# 2rfm69.net
KiCad netlist of a schematic drawn in EAGLE
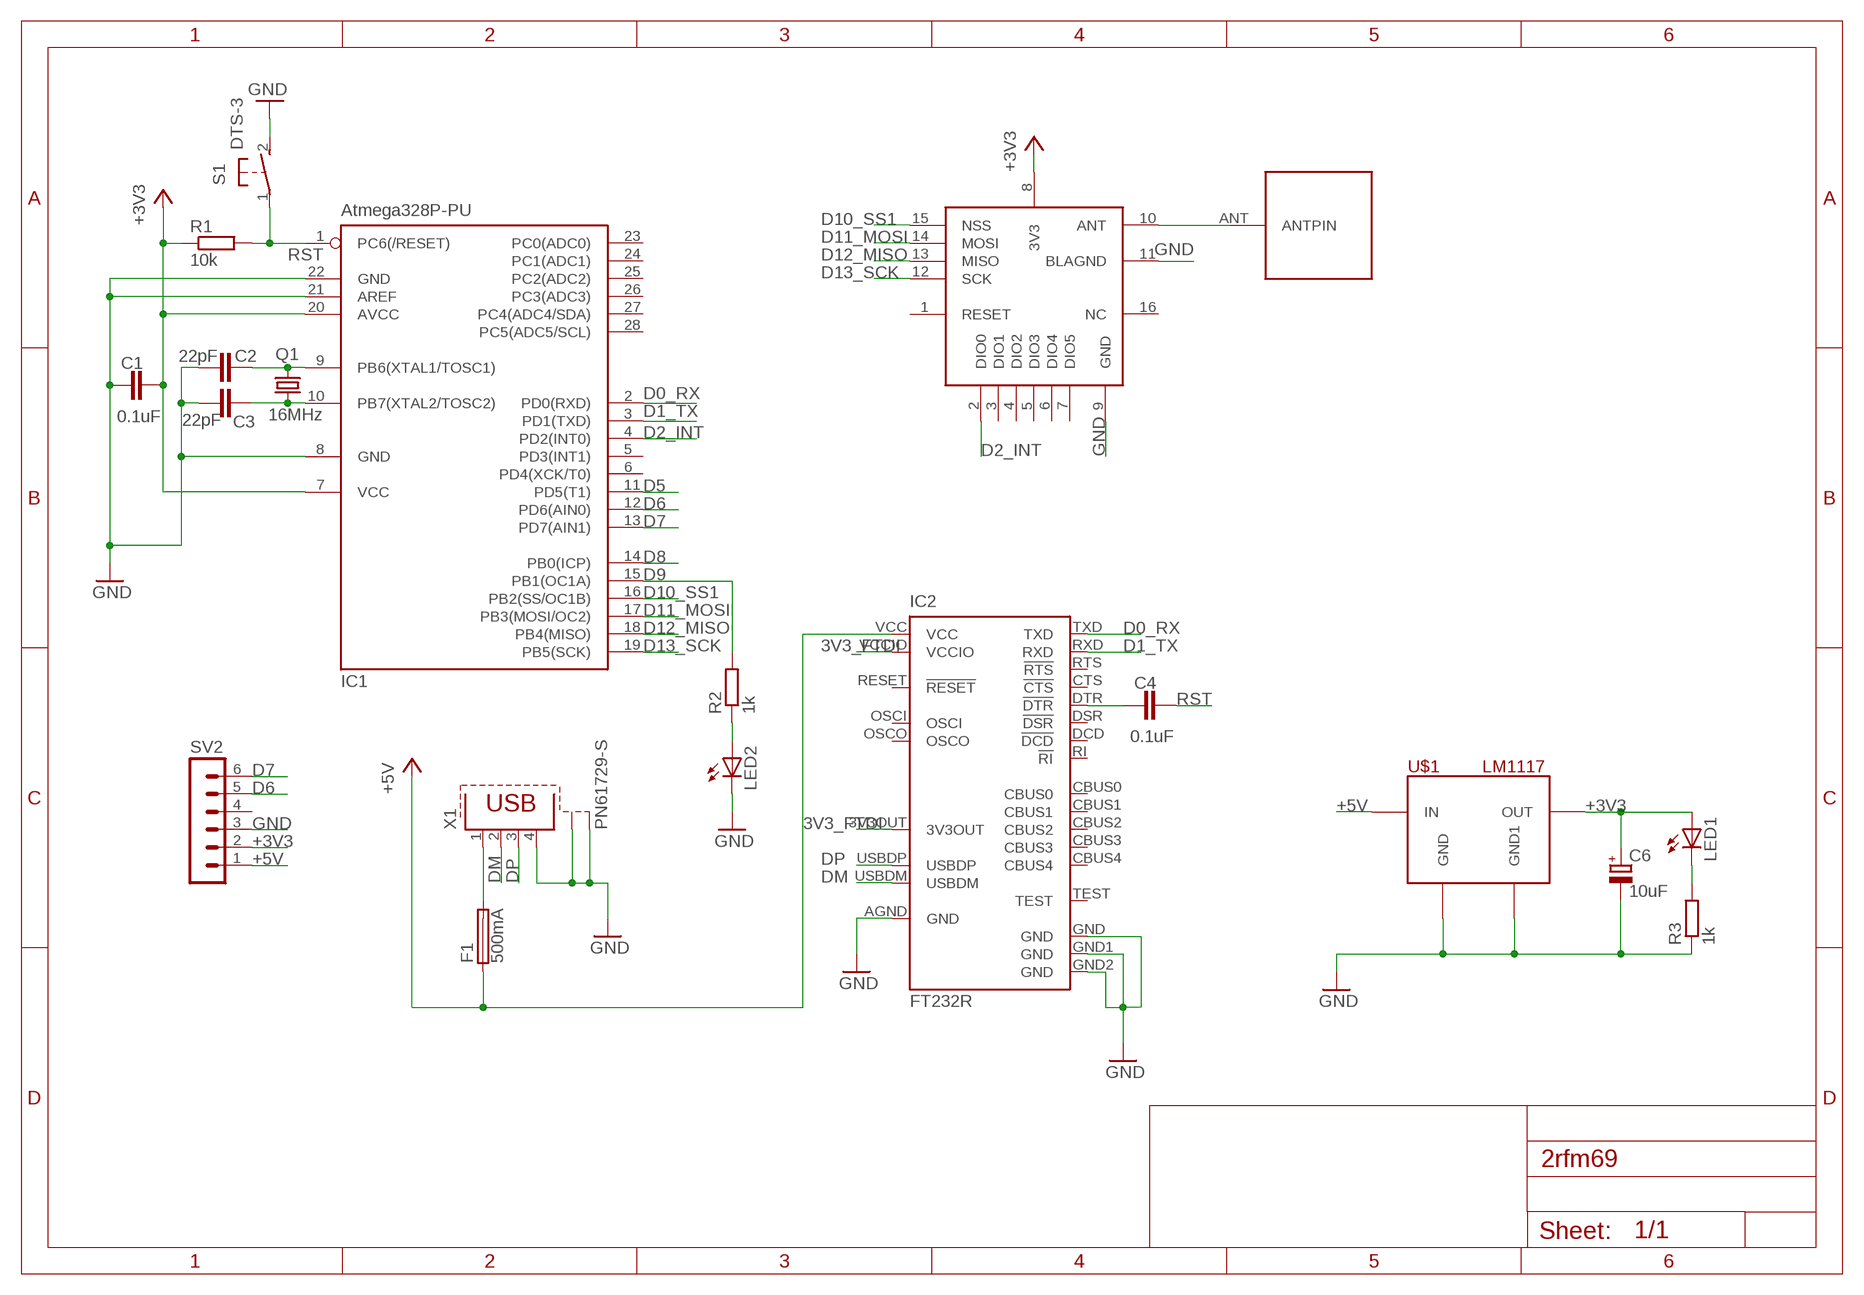
[diagram p0: schematic, sheet 1]

(export (version "E")
  (design (tool "Eeschema 10.0.6"))
  (components
    (comp (ref "C1")
      (value "0.1uF")
      (footprint "eagle-import:C050-025X075")
      (libsource (lib "eagle-import") (part "C-EU050-025X075"))
    )
    (comp (ref "C2")
      (value "22pF")
      (footprint "eagle-import:C050-025X075")
      (libsource (lib "eagle-import") (part "C-EU050-025X075"))
    )
    (comp (ref "C3")
      (value "22pF")
      (footprint "eagle-import:C050-025X075")
      (libsource (lib "eagle-import") (part "C-EU050-025X075"))
    )
    (comp (ref "C4")
      (value "0.1uF")
      (footprint "eagle-import:C050-025X075")
      (libsource (lib "eagle-import") (part "C-EU050-025X075"))
    )
    (comp (ref "C6")
      (value "10uF")
      (footprint "eagle-import:E2,5-6E")
      (libsource (lib "eagle-import") (part "CPOL-EUE2,5-6E"))
    )
    (comp (ref "F1")
      (value "500mA")
      (footprint "eagle-import:TE5")
      (libsource (lib "eagle-import") (part "TE5"))
    )
    (comp (ref "IC1")
      (value "Atmega328P-PU")
      (footprint "eagle-import:DIL28-3")
      (libsource (lib "eagle-import") (part "MEGA8-P"))
    )
    (comp (ref "IC2")
      (value "FT232R")
      (footprint "eagle-import:DIL28-6")
      (libsource (lib "eagle-import") (part "FT232R"))
    )
    (comp (ref "LED1")
      (value "LED3MM")
      (footprint "eagle-import:LED3MM")
      (libsource (lib "eagle-import") (part "LED3MM"))
    )
    (comp (ref "LED2")
      (value "LED3MM")
      (footprint "eagle-import:LED3MM")
      (libsource (lib "eagle-import") (part "LED3MM"))
    )
    (comp (ref "Q1")
      (value "16MHz")
      (footprint "eagle-import:HC49_S")
      (libsource (lib "eagle-import") (part "CRYSTALHC49S"))
    )
    (comp (ref "R1")
      (value "10k")
      (footprint "eagle-import:0204_7")
      (libsource (lib "eagle-import") (part "R-EU_0204/7"))
    )
    (comp (ref "R2")
      (value "1k")
      (footprint "eagle-import:0204_7")
      (libsource (lib "eagle-import") (part "R-EU_0204/7"))
    )
    (comp (ref "R3")
      (value "1k")
      (footprint "eagle-import:0204_7")
      (libsource (lib "eagle-import") (part "R-EU_0204/7"))
    )
    (comp (ref "S1")
      (value "DTS-3")
      (footprint "eagle-import:DTS-3")
      (libsource (lib "eagle-import") (part "DTS-3"))
    )
    (comp (ref "SV2")
      (value "MA06-1")
      (footprint "eagle-import:MA06-1")
      (libsource (lib "eagle-import") (part "MA06-1"))
    )
    (comp (ref "U$1")
      (value "LM1117")
      (footprint "eagle-import:SOT223")
      (libsource (lib "eagle-import") (part "LM1117"))
    )
    (comp (ref "U$2")
      (value "ANT")
      (footprint "eagle-import:ANT")
      (libsource (lib "eagle-import") (part "ANT"))
    )
    (comp (ref "U1")
      (value "RFM69")
      (footprint "eagle-import:RFM69")
      (libsource (lib "eagle-import") (part "RFM692"))
    )
    (comp (ref "X1")
      (value "PN61729-S")
      (footprint "eagle-import:PN61729-S")
      (libsource (lib "eagle-import") (part "PN61729-S"))
    )
  )
  (nets
    (net (code "1") (name "+3V3") (class "Default")
      (node (ref "C1") (pin "2") (pinfunction "2_2") (pintype "passive"))
      (node (ref "C6") (pin "+") (pinfunction "+_+") (pintype "passive"))
      (node (ref "IC1") (pin "20") (pinfunction "AVCC_20") (pintype "power_in"))
      (node (ref "IC1") (pin "7") (pinfunction "VCC_7") (pintype "power_in"))
      (node (ref "LED1") (pin "A") (pinfunction "A_A") (pintype "passive"))
      (node (ref "R1") (pin "1") (pinfunction "1_1") (pintype "passive"))
      (node (ref "SV2") (pin "2") (pinfunction "2_2") (pintype "passive"))
      (node (ref "U$1") (pin "VOUT") (pinfunction "OUT_VOUT") (pintype "bidirectional"))
      (node (ref "U1") (pin "8") (pinfunction "3V3_8") (pintype "bidirectional"))
    )
    (net (code "2") (name "+5V") (class "Default")
      (node (ref "F1") (pin "1") (pinfunction "1_1") (pintype "passive"))
      (node (ref "IC2") (pin "VCC") (pinfunction "VCC_VCC") (pintype "power_in"))
      (node (ref "SV2") (pin "1") (pinfunction "1_1") (pintype "passive"))
      (node (ref "U$1") (pin "VIN") (pinfunction "IN_VIN") (pintype "bidirectional"))
    )
    (net (code "3") (name "/3V3_FTDI") (class "Default")
      (node (ref "IC2") (pin "3V3OUT") (pinfunction "3V3OUT_3V3OUT") (pintype "output"))
      (node (ref "IC2") (pin "VCCIO") (pinfunction "VCCIO_VCCIO") (pintype "power_in"))
    )
    (net (code "4") (name "/D0_RX") (class "Default")
      (node (ref "IC1") (pin "2") (pinfunction "PD0(RXD)_2") (pintype "bidirectional"))
      (node (ref "IC2") (pin "TXD") (pinfunction "TXD_TXD") (pintype "output"))
    )
    (net (code "5") (name "/D1_TX") (class "Default")
      (node (ref "IC1") (pin "3") (pinfunction "PD1(TXD)_3") (pintype "bidirectional"))
      (node (ref "IC2") (pin "RXD") (pinfunction "RXD_RXD") (pintype "input"))
    )
    (net (code "6") (name "/D2_INT") (class "Default")
      (node (ref "IC1") (pin "4") (pinfunction "PD2(INT0)_4") (pintype "bidirectional"))
      (node (ref "U1") (pin "2") (pinfunction "DIO0_2") (pintype "bidirectional"))
    )
    (net (code "7") (name "/D5") (class "Default")
      (node (ref "IC1") (pin "11") (pinfunction "PD5(T1)_11") (pintype "bidirectional"))
    )
    (net (code "8") (name "/D6") (class "Default")
      (node (ref "IC1") (pin "12") (pinfunction "PD6(AIN0)_12") (pintype "bidirectional"))
      (node (ref "SV2") (pin "5") (pinfunction "5_5") (pintype "passive"))
    )
    (net (code "9") (name "/D7") (class "Default")
      (node (ref "IC1") (pin "13") (pinfunction "PD7(AIN1)_13") (pintype "bidirectional"))
      (node (ref "SV2") (pin "6") (pinfunction "6_6") (pintype "passive"))
    )
    (net (code "10") (name "/D8") (class "Default")
      (node (ref "IC1") (pin "14") (pinfunction "PB0(ICP)_14") (pintype "bidirectional"))
    )
    (net (code "11") (name "/D9") (class "Default")
      (node (ref "IC1") (pin "15") (pinfunction "PB1(OC1A)_15") (pintype "bidirectional"))
      (node (ref "R2") (pin "2") (pinfunction "2_2") (pintype "passive"))
    )
    (net (code "12") (name "/D10_SS1") (class "Default")
      (node (ref "IC1") (pin "16") (pinfunction "PB2(SS/OC1B)_16") (pintype "bidirectional"))
      (node (ref "U1") (pin "15") (pinfunction "NSS_15") (pintype "bidirectional"))
    )
    (net (code "13") (name "/D11_MOSI") (class "Default")
      (node (ref "IC1") (pin "17") (pinfunction "PB3(MOSI/OC2)_17") (pintype "bidirectional"))
      (node (ref "U1") (pin "14") (pinfunction "MOSI_14") (pintype "bidirectional"))
    )
    (net (code "14") (name "/D12_MISO") (class "Default")
      (node (ref "IC1") (pin "18") (pinfunction "PB4(MISO)_18") (pintype "bidirectional"))
      (node (ref "U1") (pin "13") (pinfunction "MISO_13") (pintype "bidirectional"))
    )
    (net (code "15") (name "/D13_SCK") (class "Default")
      (node (ref "IC1") (pin "19") (pinfunction "PB5(SCK)_19") (pintype "bidirectional"))
      (node (ref "U1") (pin "12") (pinfunction "SCK_12") (pintype "bidirectional"))
    )
    (net (code "16") (name "/DM") (class "Default")
      (node (ref "IC2") (pin "USBDM") (pinfunction "USBDM_USBDM") (pintype "bidirectional"))
      (node (ref "X1") (pin "2") (pinfunction "2_2") (pintype "passive"))
    )
    (net (code "17") (name "/DP") (class "Default")
      (node (ref "IC2") (pin "USBDP") (pinfunction "USBDP_USBDP") (pintype "bidirectional"))
      (node (ref "X1") (pin "3") (pinfunction "3_3") (pintype "passive"))
    )
    (net (code "18") (name "/RST") (class "Default")
      (node (ref "C4") (pin "2") (pinfunction "2_2") (pintype "passive"))
      (node (ref "IC1") (pin "1") (pinfunction "PC6(/RESET)_1") (pintype "bidirectional"))
      (node (ref "R1") (pin "2") (pinfunction "2_2") (pintype "passive"))
      (node (ref "S1") (pin "1") (pinfunction "1_1") (pintype "passive"))
    )
    (net (code "19") (name "GND") (class "Default")
      (node (ref "C1") (pin "1") (pinfunction "1_1") (pintype "passive"))
      (node (ref "C2") (pin "1") (pinfunction "1_1") (pintype "passive"))
      (node (ref "C3") (pin "1") (pinfunction "1_1") (pintype "passive"))
      (node (ref "C6") (pin "-") (pinfunction "-_-") (pintype "passive"))
      (node (ref "IC1") (pin "21") (pinfunction "AREF_21") (pintype "passive"))
      (node (ref "IC1") (pin "22") (pinfunction "GND_22") (pintype "power_in"))
      (node (ref "IC1") (pin "8") (pinfunction "GND_8") (pintype "power_in"))
      (node (ref "IC2") (pin "AGND") (pinfunction "GND_AGND") (pintype "power_in"))
      (node (ref "IC2") (pin "GND") (pinfunction "GND_GND") (pintype "power_in"))
      (node (ref "IC2") (pin "GND1") (pinfunction "GND_GND1") (pintype "power_in"))
      (node (ref "IC2") (pin "GND2") (pinfunction "GND_GND2") (pintype "power_in"))
      (node (ref "LED2") (pin "K") (pinfunction "C_K") (pintype "passive"))
      (node (ref "R3") (pin "1") (pinfunction "1_1") (pintype "passive"))
      (node (ref "S1") (pin "2") (pinfunction "2_2") (pintype "passive"))
      (node (ref "SV2") (pin "3") (pinfunction "3_3") (pintype "passive"))
      (node (ref "U$1") (pin "GND") (pinfunction "GND_GND") (pintype "bidirectional"))
      (node (ref "U$1") (pin "GND1") (pinfunction "GND1_GND1") (pintype "bidirectional"))
      (node (ref "U1") (pin "11") (pinfunction "BLAGND_11") (pintype "input"))
      (node (ref "U1") (pin "9") (pinfunction "GND_9") (pintype "bidirectional"))
      (node (ref "X1") (pin "4") (pinfunction "4_4") (pintype "passive"))
      (node (ref "X1") (pin "S1") (pinfunction "S1_S1") (pintype "passive"))
      (node (ref "X1") (pin "S2") (pinfunction "S2_S2") (pintype "passive"))
    )
    (net (code "20") (name "Net-(F1-Pad2)") (class "Default")
      (node (ref "F1") (pin "2") (pinfunction "2_2") (pintype "passive"))
      (node (ref "X1") (pin "1") (pinfunction "1_1") (pintype "passive"))
    )
    (net (code "21") (name "Net-(IC1-PB6(XTAL1{slash}TOSC1))") (class "Default")
      (node (ref "C2") (pin "2") (pinfunction "2_2") (pintype "passive"))
      (node (ref "IC1") (pin "9") (pinfunction "PB6(XTAL1/TOSC1)_9") (pintype "bidirectional"))
      (node (ref "Q1") (pin "1") (pinfunction "1_1") (pintype "passive"))
    )
    (net (code "22") (name "Net-(IC1-PB7(XTAL2{slash}TOSC2))") (class "Default")
      (node (ref "C3") (pin "2") (pinfunction "2_2") (pintype "passive"))
      (node (ref "IC1") (pin "10") (pinfunction "PB7(XTAL2/TOSC2)_10") (pintype "bidirectional"))
      (node (ref "Q1") (pin "2") (pinfunction "2_2") (pintype "passive"))
    )
    (net (code "23") (name "Net-(IC2-~{DTR})") (class "Default")
      (node (ref "C4") (pin "1") (pinfunction "1_1") (pintype "passive"))
      (node (ref "IC2") (pin "DTR") (pinfunction "~{DTR}_DTR") (pintype "output"))
    )
    (net (code "24") (name "Net-(LED1-C)") (class "Default")
      (node (ref "LED1") (pin "K") (pinfunction "C_K") (pintype "passive"))
      (node (ref "R3") (pin "2") (pinfunction "2_2") (pintype "passive"))
    )
    (net (code "25") (name "Net-(LED2-PadA)") (class "Default")
      (node (ref "LED2") (pin "A") (pinfunction "A_A") (pintype "passive"))
      (node (ref "R2") (pin "1") (pinfunction "1_1") (pintype "passive"))
    )
    (net (code "26") (name "Net-(U$2-ANTPIN)") (class "Default")
      (node (ref "U$2") (pin "ANT") (pinfunction "ANTPIN_ANT") (pintype "bidirectional"))
      (node (ref "U1") (pin "10") (pinfunction "ANT_10") (pintype "bidirectional"))
    )
    (net (code "27") (name "unconnected-(IC1-PC0(ADC0)-Pad23)") (class "Default")
      (node (ref "IC1") (pin "23") (pinfunction "PC0(ADC0)_23") (pintype "bidirectional"))
    )
    (net (code "28") (name "unconnected-(IC1-PC1(ADC1)-Pad24)") (class "Default")
      (node (ref "IC1") (pin "24") (pinfunction "PC1(ADC1)_24") (pintype "bidirectional"))
    )
    (net (code "29") (name "unconnected-(IC1-PC2(ADC2)-Pad25)") (class "Default")
      (node (ref "IC1") (pin "25") (pinfunction "PC2(ADC2)_25") (pintype "bidirectional"))
    )
    (net (code "30") (name "unconnected-(IC1-PC3(ADC3)-Pad26)") (class "Default")
      (node (ref "IC1") (pin "26") (pinfunction "PC3(ADC3)_26") (pintype "bidirectional"))
    )
    (net (code "31") (name "unconnected-(IC1-PC4(ADC4{slash}SDA)-Pad27)") (class "Default")
      (node (ref "IC1") (pin "27") (pinfunction "PC4(ADC4/SDA)_27") (pintype "bidirectional"))
    )
    (net (code "32") (name "unconnected-(IC1-PC5(ADC5{slash}SCL)-Pad28)") (class "Default")
      (node (ref "IC1") (pin "28") (pinfunction "PC5(ADC5/SCL)_28") (pintype "bidirectional"))
    )
    (net (code "33") (name "unconnected-(IC1-PD3(INT1)-Pad5)") (class "Default")
      (node (ref "IC1") (pin "5") (pinfunction "PD3(INT1)_5") (pintype "bidirectional"))
    )
    (net (code "34") (name "unconnected-(IC1-PD4(XCK{slash}T0)-Pad6)") (class "Default")
      (node (ref "IC1") (pin "6") (pinfunction "PD4(XCK/T0)_6") (pintype "bidirectional"))
    )
    (net (code "35") (name "unconnected-(IC2-PadCBUS0)") (class "Default")
      (node (ref "IC2") (pin "CBUS0") (pinfunction "CBUS0_CBUS0") (pintype "bidirectional"))
    )
    (net (code "36") (name "unconnected-(IC2-PadCBUS1)") (class "Default")
      (node (ref "IC2") (pin "CBUS1") (pinfunction "CBUS1_CBUS1") (pintype "bidirectional"))
    )
    (net (code "37") (name "unconnected-(IC2-PadCBUS2)") (class "Default")
      (node (ref "IC2") (pin "CBUS2") (pinfunction "CBUS2_CBUS2") (pintype "bidirectional"))
    )
    (net (code "38") (name "unconnected-(IC2-PadCBUS3)") (class "Default")
      (node (ref "IC2") (pin "CBUS3") (pinfunction "CBUS3_CBUS3") (pintype "bidirectional"))
    )
    (net (code "39") (name "unconnected-(IC2-PadCBUS4)") (class "Default")
      (node (ref "IC2") (pin "CBUS4") (pinfunction "CBUS4_CBUS4") (pintype "bidirectional"))
    )
    (net (code "40") (name "unconnected-(IC2-PadOSCI)") (class "Default")
      (node (ref "IC2") (pin "OSCI") (pinfunction "OSCI_OSCI") (pintype "input"))
    )
    (net (code "41") (name "unconnected-(IC2-PadOSCO)") (class "Default")
      (node (ref "IC2") (pin "OSCO") (pinfunction "OSCO_OSCO") (pintype "output"))
    )
    (net (code "42") (name "unconnected-(IC2-PadTEST)") (class "Default")
      (node (ref "IC2") (pin "TEST") (pinfunction "TEST_TEST") (pintype "input"))
    )
    (net (code "43") (name "unconnected-(IC2-~{CTS}-PadCTS)") (class "Default")
      (node (ref "IC2") (pin "CTS") (pinfunction "~{CTS}_CTS") (pintype "input"))
    )
    (net (code "44") (name "unconnected-(IC2-~{DCD}-PadDCD)") (class "Default")
      (node (ref "IC2") (pin "DCD") (pinfunction "~{DCD}_DCD") (pintype "input"))
    )
    (net (code "45") (name "unconnected-(IC2-~{DSR}-PadDSR)") (class "Default")
      (node (ref "IC2") (pin "DSR") (pinfunction "~{DSR}_DSR") (pintype "input"))
    )
    (net (code "46") (name "unconnected-(IC2-~{RESET}-PadRESET)") (class "Default")
      (node (ref "IC2") (pin "RESET") (pinfunction "~{RESET}_RESET") (pintype "input"))
    )
    (net (code "47") (name "unconnected-(IC2-~{RI}-PadRI)") (class "Default")
      (node (ref "IC2") (pin "RI") (pinfunction "~{RI}_RI") (pintype "input"))
    )
    (net (code "48") (name "unconnected-(IC2-~{RTS}-PadRTS)") (class "Default")
      (node (ref "IC2") (pin "RTS") (pinfunction "~{RTS}_RTS") (pintype "output"))
    )
    (net (code "49") (name "unconnected-(SV2-Pad4)") (class "Default")
      (node (ref "SV2") (pin "4") (pinfunction "4_4") (pintype "passive"))
    )
    (net (code "50") (name "unconnected-(U1-DIO1-Pad3)") (class "Default")
      (node (ref "U1") (pin "3") (pinfunction "DIO1_3") (pintype "bidirectional"))
    )
    (net (code "51") (name "unconnected-(U1-DIO2-Pad4)") (class "Default")
      (node (ref "U1") (pin "4") (pinfunction "DIO2_4") (pintype "bidirectional"))
    )
    (net (code "52") (name "unconnected-(U1-DIO3-Pad5)") (class "Default")
      (node (ref "U1") (pin "5") (pinfunction "DIO3_5") (pintype "bidirectional"))
    )
    (net (code "53") (name "unconnected-(U1-DIO4-Pad6)") (class "Default")
      (node (ref "U1") (pin "6") (pinfunction "DIO4_6") (pintype "bidirectional"))
    )
    (net (code "54") (name "unconnected-(U1-DIO5-Pad7)") (class "Default")
      (node (ref "U1") (pin "7") (pinfunction "DIO5_7") (pintype "bidirectional"))
    )
    (net (code "55") (name "unconnected-(U1-NC-Pad16)") (class "Default")
      (node (ref "U1") (pin "16") (pinfunction "NC_16") (pintype "no_connect"))
    )
    (net (code "56") (name "unconnected-(U1-RESET-Pad1)") (class "Default")
      (node (ref "U1") (pin "1") (pinfunction "RESET_1") (pintype "bidirectional"))
    )
  )
)
